# Battery_Manager.net
KiCad netlist of a schematic drawn in Altium Designer
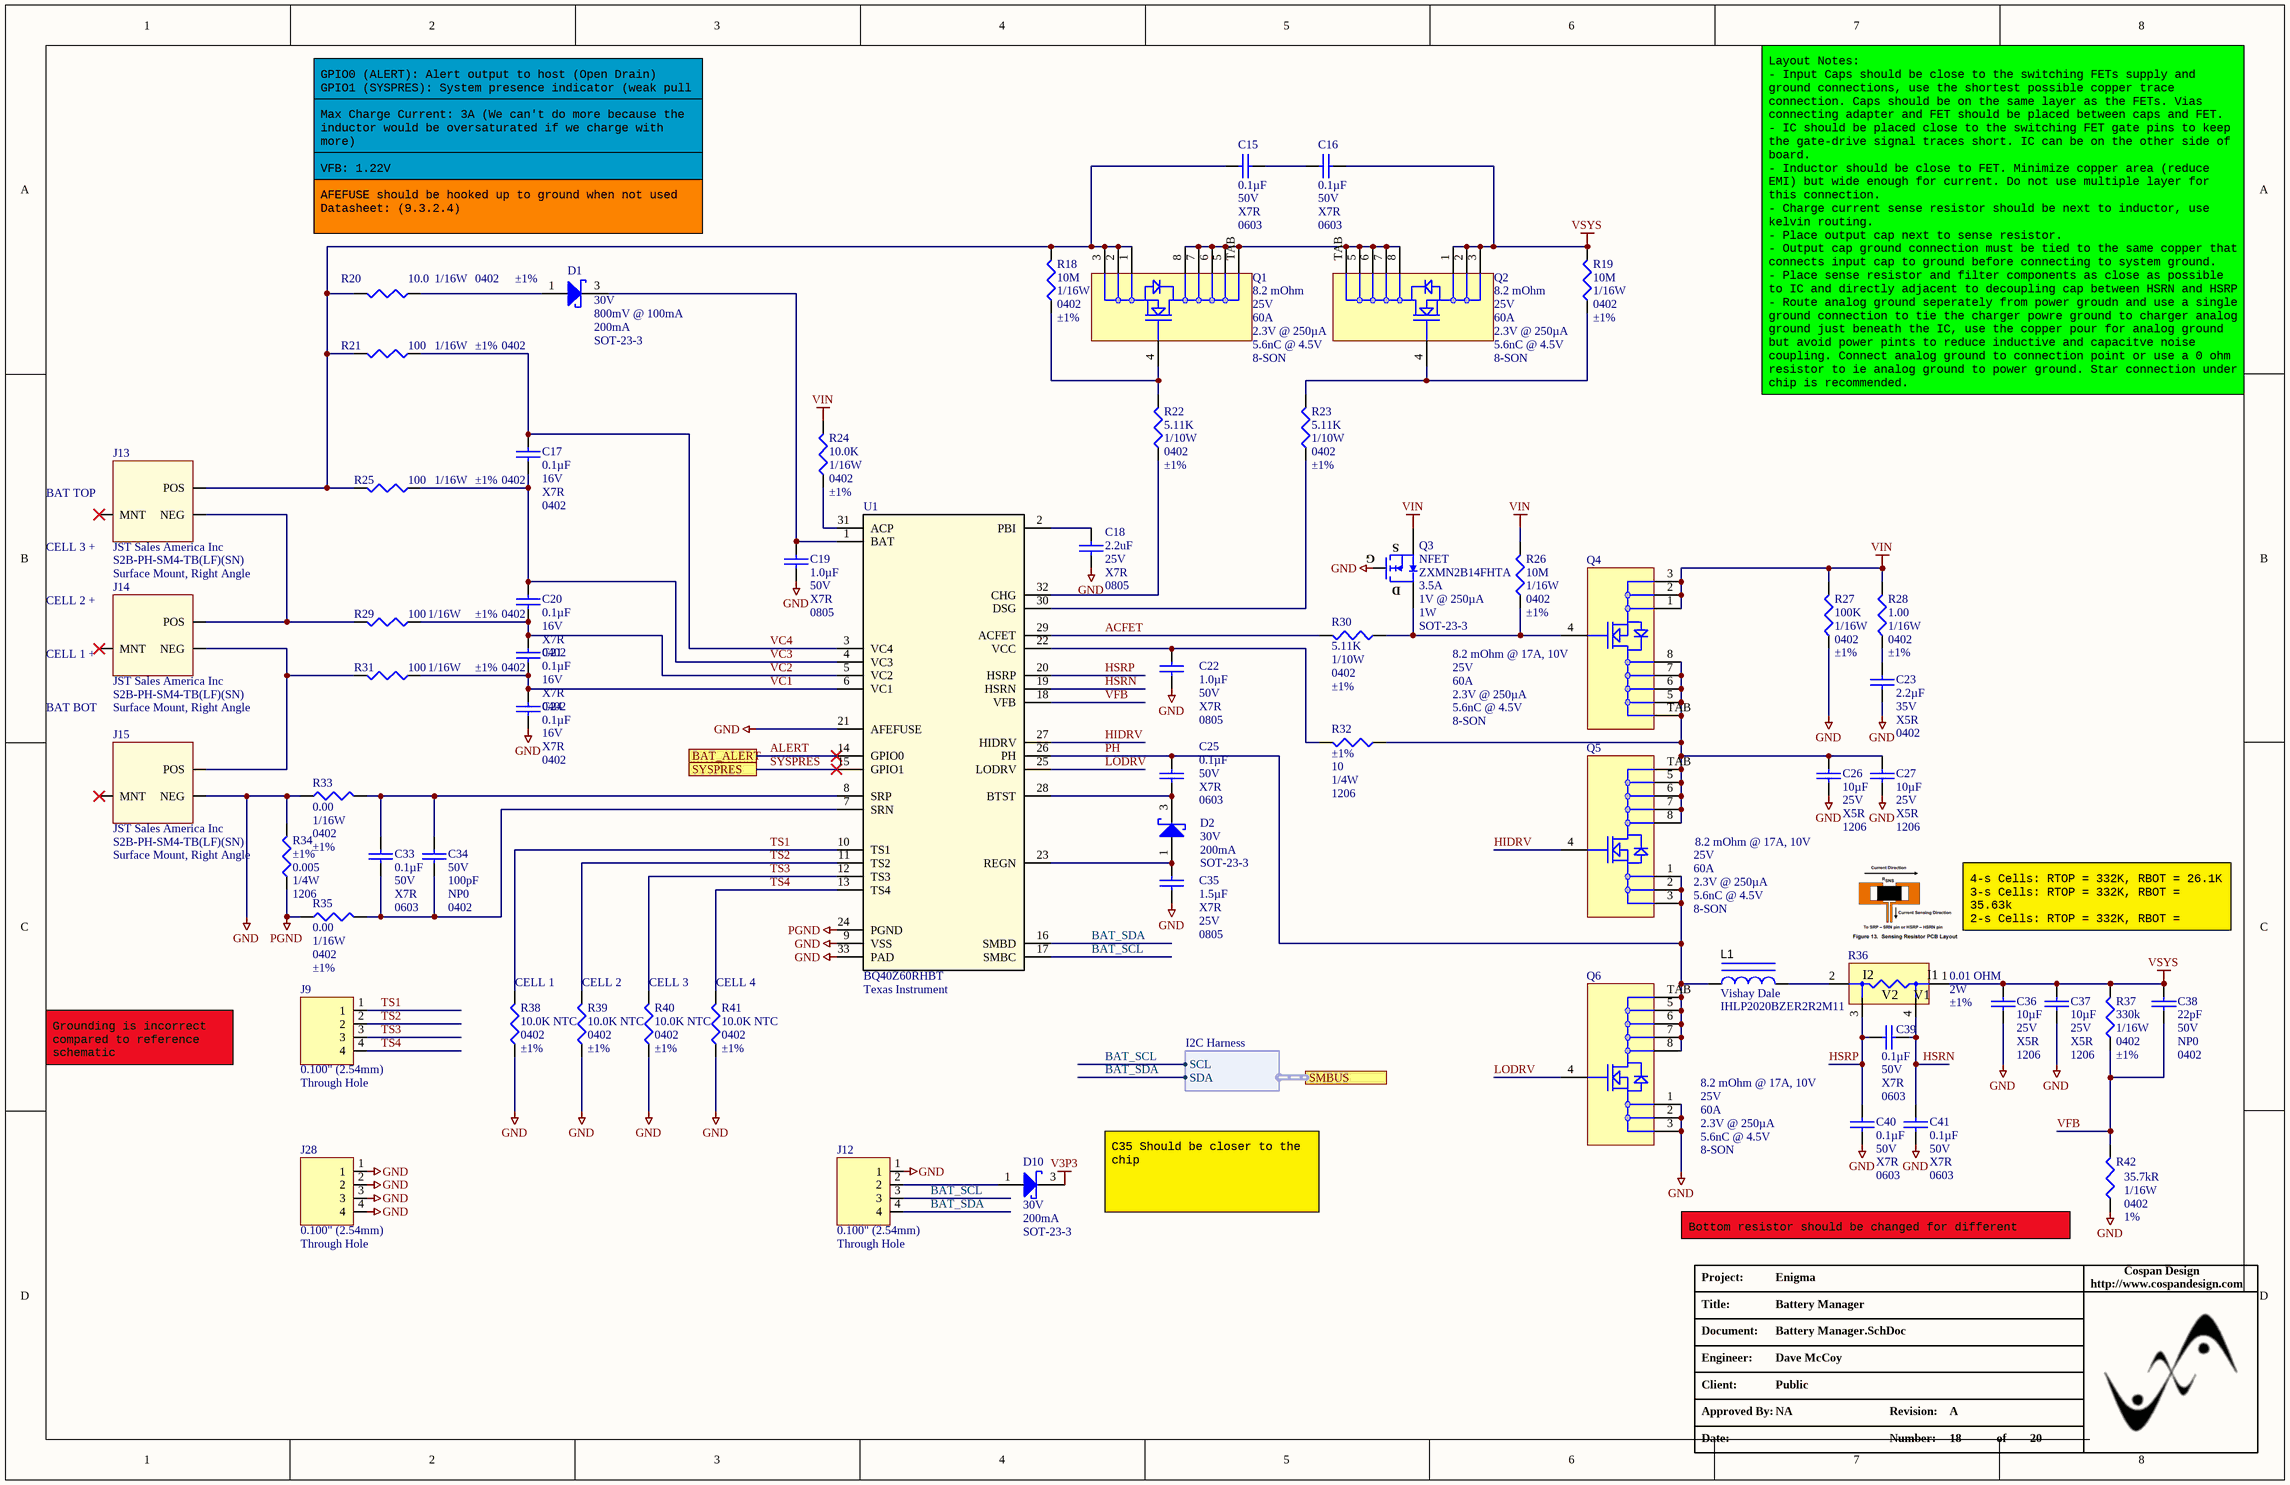
[diagram p0: Battery Manager.SchDoc]

(export (version "E")
  (design (tool "Eeschema 10.0.6"))
  (components
    (comp (ref "C15")
      (value "C_0603_0.1µF")
      (footprint "C_ERA-0603")
      (description "CAP CER 0.1UF 50V X7R 0603")
      (fields
        (field (name "MANUFACTURER") "Samsung Electro-Mechanics America, Inc.")
        (field (name "MANUFACTURER PART NUMBER") "CL10B104KB8SFNC")
        (field (name "CAPACITANCE") "0.1µF")
        (field (name "VOLTAGE - RATED") "50V")
        (field (name "TEMPERATURE COEFFICIENT") "X7R")
        (field (name "PACKAGE / CASE") "0603")
      )
      (libsource (lib "Cospan Design") (part "C_0603_0.1µF"))
    )
    (comp (ref "C16")
      (value "C_0603_0.1µF")
      (footprint "C_ERA-0603")
      (description "CAP CER 0.1UF 50V X7R 0603")
      (fields
        (field (name "MANUFACTURER") "Samsung Electro-Mechanics America, Inc.")
        (field (name "MANUFACTURER PART NUMBER") "CL10B104KB8SFNC")
        (field (name "CAPACITANCE") "0.1µF")
        (field (name "VOLTAGE - RATED") "50V")
        (field (name "TEMPERATURE COEFFICIENT") "X7R")
        (field (name "PACKAGE / CASE") "0603")
      )
      (libsource (lib "Cospan Design") (part "C_0603_0.1µF"))
    )
    (comp (ref "C17")
      (value "0.1uF")
      (footprint "C_0402")
      (description "CAP CER .10UF 16V X7R 0402")
      (fields
        (field (name "MANUFACTURER") "Murata Electronics North America")
        (field (name "MANUFACTURER PART NUMBER") "GRM155R71C104KA88J")
        (field (name "CAPACITANCE") "0.1µF")
        (field (name "VOLTAGE - RATED") "16V")
        (field (name "TEMPERATURE COEFFICIENT") "X7R")
        (field (name "PACKAGE / CASE") "0402")
      )
      (libsource (lib "Main LibraryX") (part "C_0402_0.1UF_16V"))
    )
    (comp (ref "C18")
      (value "C_0805_2.2uF_25V")
      (footprint "C_ERA-0805")
      (fields
        (field (name "MANUFACTURER") "Taiyo Yuden")
        (field (name "MANUFACTURER PART NUMBER") "TMK212B7225KG-TR")
        (field (name "TOLERANCE") "±10%")
        (field (name "CAPACITANCE") "2.2uF")
        (field (name "VOLTAGE - RATED") "25V")
        (field (name "TEMPERATURE COEFFICIENT") "X7R")
        (field (name "PACKAGE / CASE") "0805")
      )
      (libsource (lib "Cospan Design") (part "C_0805_2.2uF_25V"))
    )
    (comp (ref "C19")
      (value "1.0uF")
      (footprint "C_ERA-0805")
      (description "CAP CER 1UF 50V X7R 0805")
      (fields
        (field (name "MANUFACTURER") "Murata Electronics North America")
        (field (name "MANUFACTURER PART NUMBER") "GRM21BR71H105KA12L")
        (field (name "CAPACITANCE") "1.0µF")
        (field (name "VOLTAGE - RATED") "50V")
        (field (name "TEMPERATURE COEFFICIENT") "X7R")
        (field (name "PACKAGE / CASE") "0805")
      )
      (libsource (lib "Main Library") (part "C_0805_1.0uF_50V"))
    )
    (comp (ref "C20")
      (value "0.1uF")
      (footprint "C_0402")
      (description "CAP CER .10UF 16V X7R 0402")
      (fields
        (field (name "MANUFACTURER") "Murata Electronics North America")
        (field (name "MANUFACTURER PART NUMBER") "GRM155R71C104KA88J")
        (field (name "CAPACITANCE") "0.1µF")
        (field (name "VOLTAGE - RATED") "16V")
        (field (name "TEMPERATURE COEFFICIENT") "X7R")
        (field (name "PACKAGE / CASE") "0402")
      )
      (libsource (lib "Main LibraryX") (part "C_0402_0.1UF_16V"))
    )
    (comp (ref "C21")
      (value "0.1uF")
      (footprint "C_0402")
      (description "CAP CER .10UF 16V X7R 0402")
      (fields
        (field (name "MANUFACTURER") "Murata Electronics North America")
        (field (name "MANUFACTURER PART NUMBER") "GRM155R71C104KA88J")
        (field (name "CAPACITANCE") "0.1µF")
        (field (name "VOLTAGE - RATED") "16V")
        (field (name "TEMPERATURE COEFFICIENT") "X7R")
        (field (name "PACKAGE / CASE") "0402")
      )
      (libsource (lib "Main LibraryX") (part "C_0402_0.1UF_16V"))
    )
    (comp (ref "C22")
      (value "1.0uF")
      (footprint "C_ERA-0805")
      (description "CAP CER 1UF 50V X7R 0805")
      (fields
        (field (name "MANUFACTURER") "Murata Electronics North America")
        (field (name "MANUFACTURER PART NUMBER") "GRM21BR71H105KA12L")
        (field (name "CAPACITANCE") "1.0µF")
        (field (name "VOLTAGE - RATED") "50V")
        (field (name "TEMPERATURE COEFFICIENT") "X7R")
        (field (name "PACKAGE / CASE") "0805")
      )
      (libsource (lib "Main Library") (part "C_0805_1.0uF_50V"))
    )
    (comp (ref "C23")
      (value "C_0402_2.2uF_35V")
      (footprint "C_ERA-0402")
      (description "CAP CER 2.2UF 35V 20% X5R 0402")
      (fields
        (field (name "MANUFACTURER") "TDK Corporation")
        (field (name "MANUFACTURER PART NUMBER") "C1005X5R1V225K050BC")
        (field (name "CAPACITANCE") "2.2µF")
        (field (name "VOLTAGE - RATED") "35V")
        (field (name "TEMPERATURE COEFFICIENT") "X5R")
        (field (name "PACKAGE / CASE") "0402")
      )
      (libsource (lib "Main LibraryX") (part "C_0402_2.2uF_35V"))
    )
    (comp (ref "C24")
      (value "0.1uF")
      (footprint "C_0402")
      (description "CAP CER .10UF 16V X7R 0402")
      (fields
        (field (name "MANUFACTURER") "Murata Electronics North America")
        (field (name "MANUFACTURER PART NUMBER") "GRM155R71C104KA88J")
        (field (name "CAPACITANCE") "0.1µF")
        (field (name "VOLTAGE - RATED") "16V")
        (field (name "TEMPERATURE COEFFICIENT") "X7R")
        (field (name "PACKAGE / CASE") "0402")
      )
      (libsource (lib "Main LibraryX") (part "C_0402_0.1UF_16V"))
    )
    (comp (ref "C25")
      (value "C_0603_0.1µF")
      (footprint "C_ERA-0603")
      (description "CAP CER 0.1UF 50V X7R 0603")
      (fields
        (field (name "MANUFACTURER") "Samsung Electro-Mechanics America, Inc.")
        (field (name "MANUFACTURER PART NUMBER") "CL10B104KB8SFNC")
        (field (name "CAPACITANCE") "0.1µF")
        (field (name "VOLTAGE - RATED") "50V")
        (field (name "TEMPERATURE COEFFICIENT") "X7R")
        (field (name "PACKAGE / CASE") "0603")
      )
      (libsource (lib "Cospan Design") (part "C_0603_0.1µF"))
    )
    (comp (ref "C26")
      (value "10µF")
      (footprint "CAP-1206")
      (description "CAP CER 10UF 25V X5R 1206")
      (fields
        (field (name "MANUFACTURER") "Murata Electronics North America")
        (field (name "MANUFACTURER PART NUMBER") "GRM31CR61E106MA12L")
        (field (name "CAPACITANCE") "10µF")
        (field (name "VOLTAGE - RATED") "25V")
        (field (name "TEMPERATURE COEFFICIENT") "X5R")
        (field (name "PACKAGE / CASE") "1206")
      )
      (libsource (lib "Main Library") (part "C_1206_10UF_25V"))
    )
    (comp (ref "C27")
      (value "10µF")
      (footprint "CAP-1206")
      (description "CAP CER 10UF 25V X5R 1206")
      (fields
        (field (name "MANUFACTURER") "Murata Electronics North America")
        (field (name "MANUFACTURER PART NUMBER") "GRM31CR61E106MA12L")
        (field (name "CAPACITANCE") "10µF")
        (field (name "VOLTAGE - RATED") "25V")
        (field (name "TEMPERATURE COEFFICIENT") "X5R")
        (field (name "PACKAGE / CASE") "1206")
      )
      (libsource (lib "Main Library") (part "C_1206_10UF_25V"))
    )
    (comp (ref "C33")
      (value "C_0603_0.1µF")
      (footprint "C_ERA-0603")
      (description "CAP CER 0.1UF 50V X7R 0603")
      (fields
        (field (name "MANUFACTURER") "Samsung Electro-Mechanics America, Inc.")
        (field (name "MANUFACTURER PART NUMBER") "CL10B104KB8SFNC")
        (field (name "CAPACITANCE") "0.1µF")
        (field (name "VOLTAGE - RATED") "50V")
        (field (name "TEMPERATURE COEFFICIENT") "X7R")
        (field (name "PACKAGE / CASE") "0603")
      )
      (libsource (lib "Cospan Design") (part "C_0603_0.1µF"))
    )
    (comp (ref "C34")
      (value "100pF")
      (footprint "C_0402")
      (description "CAP CER 100PF 50V 5% C0G 0402")
      (fields
        (field (name "MANUFACTURER") "Murata Electronics North America")
        (field (name "MANUFACTURER PART NUMBER") "GRM1555C1H101JA01D")
        (field (name "VOLTAGE - RATED") "50V")
        (field (name "CAPACITANCE") "100pF")
        (field (name "TEMPERATURE COEFFICIENT") "NP0")
        (field (name "PACKAGE / CASE") "0402")
      )
      (libsource (lib "Main LibraryX") (part "C_0402_100PF"))
    )
    (comp (ref "C35")
      (value "C_0805_1.5uF_25V")
      (footprint "C_ERA-0805")
      (description "1.5µF ±10% 25V Ceramic Capacitor X7R 0805 (2012 Metric)")
      (fields
        (field (name "MANUFACTURER") "Murata Electronics North America")
        (field (name "MANUFACTURER PART NUMBER") "GRM21BR71E155KA88L")
        (field (name "CAPACITANCE") "1.5µF")
        (field (name "VOLTAGE - RATED") "X7R")
        (field (name "TEMPERATURE COEFFICIENT") "25V")
        (field (name "PACKAGE / CASE") "0805")
      )
      (libsource (lib "Cospan Design") (part "C_0805_1.5uF_25V"))
    )
    (comp (ref "C36")
      (value "10µF")
      (footprint "CAP-1206")
      (description "CAP CER 10UF 25V X5R 1206")
      (fields
        (field (name "MANUFACTURER") "Murata Electronics North America")
        (field (name "MANUFACTURER PART NUMBER") "GRM31CR61E106MA12L")
        (field (name "CAPACITANCE") "10µF")
        (field (name "VOLTAGE - RATED") "25V")
        (field (name "TEMPERATURE COEFFICIENT") "X5R")
        (field (name "PACKAGE / CASE") "1206")
      )
      (libsource (lib "Main Library") (part "C_1206_10UF_25V"))
    )
    (comp (ref "C37")
      (value "10µF")
      (footprint "CAP-1206")
      (description "CAP CER 10UF 25V X5R 1206")
      (fields
        (field (name "MANUFACTURER") "Murata Electronics North America")
        (field (name "MANUFACTURER PART NUMBER") "GRM31CR61E106MA12L")
        (field (name "CAPACITANCE") "10µF")
        (field (name "VOLTAGE - RATED") "25V")
        (field (name "TEMPERATURE COEFFICIENT") "X5R")
        (field (name "PACKAGE / CASE") "1206")
      )
      (libsource (lib "Main Library") (part "C_1206_10UF_25V"))
    )
    (comp (ref "C38")
      (value "22pF")
      (footprint "C_ERA-0402")
      (description "CAP CER 22PF 50V NP0 0402")
      (fields
        (field (name "MANUFACTURER") "Murata Electronics North America")
        (field (name "MANUFACTURER PART NUMBER") "GRM1555C1H220FA01D")
        (field (name "CAPACITANCE") "22pF")
        (field (name "VOLTAGE - RATED") "50V")
        (field (name "TEMPERATURE COEFFICIENT") "NP0")
        (field (name "PACKAGE / CASE") "0402")
      )
      (libsource (lib "Main LibraryX") (part "C_0402_22PF_50V"))
    )
    (comp (ref "C39")
      (value "C_0603_0.1µF")
      (footprint "C_ERA-0603")
      (description "CAP CER 0.1UF 50V X7R 0603")
      (fields
        (field (name "MANUFACTURER") "Samsung Electro-Mechanics America, Inc.")
        (field (name "MANUFACTURER PART NUMBER") "CL10B104KB8SFNC")
        (field (name "CAPACITANCE") "0.1µF")
        (field (name "VOLTAGE - RATED") "50V")
        (field (name "TEMPERATURE COEFFICIENT") "X7R")
        (field (name "PACKAGE / CASE") "0603")
      )
      (libsource (lib "Cospan Design") (part "C_0603_0.1µF"))
    )
    (comp (ref "C40")
      (value "C_0603_0.1µF")
      (footprint "C_ERA-0603")
      (description "CAP CER 0.1UF 50V X7R 0603")
      (fields
        (field (name "MANUFACTURER") "Samsung Electro-Mechanics America, Inc.")
        (field (name "MANUFACTURER PART NUMBER") "CL10B104KB8SFNC")
        (field (name "CAPACITANCE") "0.1µF")
        (field (name "VOLTAGE - RATED") "50V")
        (field (name "TEMPERATURE COEFFICIENT") "X7R")
        (field (name "PACKAGE / CASE") "0603")
      )
      (libsource (lib "Cospan Design") (part "C_0603_0.1µF"))
    )
    (comp (ref "C41")
      (value "C_0603_0.1µF")
      (footprint "C_ERA-0603")
      (description "CAP CER 0.1UF 50V X7R 0603")
      (fields
        (field (name "MANUFACTURER") "Samsung Electro-Mechanics America, Inc.")
        (field (name "MANUFACTURER PART NUMBER") "CL10B104KB8SFNC")
        (field (name "CAPACITANCE") "0.1µF")
        (field (name "VOLTAGE - RATED") "50V")
        (field (name "TEMPERATURE COEFFICIENT") "X7R")
        (field (name "PACKAGE / CASE") "0603")
      )
      (libsource (lib "Cospan Design") (part "C_0603_0.1µF"))
    )
    (comp (ref "D1")
      (value "BAT54")
      (footprint "SOT23")
      (description "DIODE SCHOTTKY 30V 200MA SOT-23")
      (fields
        (field (name "MANUFACTURER") "Fairchild Semiconductor")
        (field (name "VOLTAGE - DC REVERSE (VR) (MAX)") "30V")
        (field (name "VOLTAGE - FORWARD (VF) (MAX) @ IF") "800mV @ 100mA")
        (field (name "CURRENT - AVERAGE RECTIFIED (IO)") "200mA")
        (field (name "PACKAGE / CASE") "SOT-23-3")
      )
      (libsource (lib "Main Library") (part "D_SCHOTT_BAT54"))
    )
    (comp (ref "D2")
      (value "BAT54")
      (footprint "SOT23")
      (description "DIODE SCHOTTKY 30V 200MA SOT-23")
      (fields
        (field (name "MANUFACTURER") "Fairchild Semiconductor")
        (field (name "VOLTAGE - DC REVERSE (VR) (MAX)") "30V")
        (field (name "CURRENT - AVERAGE RECTIFIED (IO)") "200mA")
        (field (name "PACKAGE / CASE") "SOT-23-3")
      )
      (libsource (lib "Main Library") (part "D_SCHOTT_BAT54"))
    )
    (comp (ref "D10")
      (value "BAT54")
      (footprint "SOT23")
      (description "DIODE SCHOTTKY 30V 200MA SOT-23")
      (fields
        (field (name "MANUFACTURER") "Fairchild Semiconductor")
        (field (name "VOLTAGE - DC REVERSE (VR) (MAX)") "30V")
        (field (name "CURRENT - AVERAGE RECTIFIED (IO)") "200mA")
        (field (name "PACKAGE / CASE") "SOT-23-3")
      )
      (libsource (lib "Main Library") (part "D_SCHOTT_BAT54"))
    )
    (comp (ref "J9")
      (value "J_HDR1X4_THRHOLE_VERT")
      (footprint "HDR_1X4")
      (description "CONN HEADER .100\" 4POS TIN PCB")
      (fields
        (field (name "MANUFACTURER") "Samtec")
        (field (name "MANUFACTURER PART NUMBER") "TSW-104-07-T-S")
        (field (name "PITCH") "0.100\" (2.54mm)")
        (field (name "MOUNTING TYPE") "Through Hole")
      )
      (libsource (lib "Main Library") (part "J_HDR1X4_THRHOLE_VERT"))
    )
    (comp (ref "J12")
      (value "J_HDR1X4_THRHOLE_VERT")
      (footprint "HDR_1X4")
      (description "CONN HEADER .100\" 4POS TIN PCB")
      (fields
        (field (name "MANUFACTURER") "Samtec")
        (field (name "MANUFACTURER PART NUMBER") "TSW-104-07-T-S")
        (field (name "PITCH") "0.100\" (2.54mm)")
        (field (name "MOUNTING TYPE") "Through Hole")
      )
      (libsource (lib "Main Library") (part "J_HDR1X4_THRHOLE_VERT"))
    )
    (comp (ref "J13")
      (value "J_LIPO_BAT_CONNECTOR")
      (footprint "HDR_1X2_LIPO_BATTERY")
      (description "CONN HEADER PH SIDE 2POS 2MM SMD")
      (fields
        (field (name "MANUFACTURER") "JST Sales America Inc")
        (field (name "MANUFACTURER PART NUMBER") "S2B-PH-SM4-TB(LF)(SN)")
        (field (name "MOUNTING TYPE") "Surface Mount, Right Angle")
      )
      (libsource (lib "Main Library") (part "J_LIPO_BAT_CONNECTOR"))
    )
    (comp (ref "J14")
      (value "J_LIPO_BAT_CONNECTOR")
      (footprint "HDR_1X2_LIPO_BATTERY")
      (description "CONN HEADER PH SIDE 2POS 2MM SMD")
      (fields
        (field (name "MANUFACTURER") "JST Sales America Inc")
        (field (name "MANUFACTURER PART NUMBER") "S2B-PH-SM4-TB(LF)(SN)")
        (field (name "MOUNTING TYPE") "Surface Mount, Right Angle")
      )
      (libsource (lib "Main Library") (part "J_LIPO_BAT_CONNECTOR"))
    )
    (comp (ref "J15")
      (value "J_LIPO_BAT_CONNECTOR")
      (footprint "HDR_1X2_LIPO_BATTERY")
      (description "CONN HEADER PH SIDE 2POS 2MM SMD")
      (fields
        (field (name "MANUFACTURER") "JST Sales America Inc")
        (field (name "MANUFACTURER PART NUMBER") "S2B-PH-SM4-TB(LF)(SN)")
        (field (name "MOUNTING TYPE") "Surface Mount, Right Angle")
      )
      (libsource (lib "Main Library") (part "J_LIPO_BAT_CONNECTOR"))
    )
    (comp (ref "J28")
      (value "J_HDR1X4_THRHOLE_VERT")
      (footprint "HDR_1X4")
      (description "CONN HEADER .100\" 4POS TIN PCB")
      (fields
        (field (name "MANUFACTURER") "Samtec")
        (field (name "MANUFACTURER PART NUMBER") "TSW-104-07-T-S")
        (field (name "PITCH") "0.100\" (2.54mm)")
        (field (name "MOUNTING TYPE") "Through Hole")
      )
      (libsource (lib "Main Library") (part "J_HDR1X4_THRHOLE_VERT"))
    )
    (comp (ref "L1")
      (value "L_IHLP2020BZER2R2M11")
      (footprint "IHLP-2020BZ")
      (description "2.2µH Shielded Molded Inductor 5A 37.7 mOhm Max")
      (fields
        (field (name "TOLERANCE") "±20%")
        (field (name "MANUFACTURER") "Vishay Dale")
        (field (name "MANUFACTURER PART NUMBER") "IHLP2020BZER2R2M11")
      )
      (libsource (lib "Cospan Design") (part "L_IHLP2020BZER2R2M11"))
    )
    (comp (ref "Q1")
      (value "N-Channel Nex_FET")
      (footprint "Q_TDSON-8 NexFET")
      (description "MOSFET N-CH 25V 60A 8-SON")
      (fields
        (field (name "MANUFACTURER") "Texas Instruments")
        (field (name "MANUFACTURER PART NUMBER") "CSD16409Q3")
        (field (name "RDS ON (MAX) @ ID, VGS") "8.2 mOhm")
        (field (name "DRAIN TO SOURCE VOLTAGE (VDSS)") "25V")
        (field (name "CURRENT - CONTINUOUS DRAIN (ID) @ 25° C") "60A")
        (field (name "VGS(TH) (MAX) @ ID") "2.3V @ 250µA")
        (field (name "GATE CHARGE (QG) @ VGS") "5.6nC @ 4.5V")
        (field (name "PACKAGE / CASE") "8-SON")
      )
      (libsource (lib "Main Library") (part "Q_N-CH_8SON_60A_9.5mOHM"))
    )
    (comp (ref "Q2")
      (value "N-Channel Nex_FET")
      (footprint "Q_TDSON-8 NexFET")
      (description "MOSFET N-CH 25V 60A 8-SON")
      (fields
        (field (name "MANUFACTURER") "Texas Instruments")
        (field (name "MANUFACTURER PART NUMBER") "CSD16409Q3")
        (field (name "RDS ON (MAX) @ ID, VGS") "8.2 mOhm")
        (field (name "DRAIN TO SOURCE VOLTAGE (VDSS)") "25V")
        (field (name "CURRENT - CONTINUOUS DRAIN (ID) @ 25° C") "60A")
        (field (name "VGS(TH) (MAX) @ ID") "2.3V @ 250µA")
        (field (name "GATE CHARGE (QG) @ VGS") "5.6nC @ 4.5V")
        (field (name "PACKAGE / CASE") "8-SON")
      )
      (libsource (lib "Main Library") (part "Q_N-CH_8SON_60A_9.5mOHM"))
    )
    (comp (ref "Q3")
      (value "NFET")
      (footprint "SOT-23A")
      (description "MOSFET N-CH 20V 3.5A SOT23-3")
      (fields
        (field (name "MANUFACTURER") "Diodes/Zetex")
        (field (name "MANUFACTURER PART NUMBER") "ZXMN2B14FHTA")
        (field (name "CURRENT - CONTINUOUS DRAIN (ID) @ 25° C") "3.5A")
        (field (name "VGS(TH) (MAX) @ ID") "1V @ 250µA")
        (field (name "POWER - MAX") "1W")
        (field (name "PACKAGE / CASE") "SOT-23-3")
      )
      (libsource (lib "Main LibraryX") (part "Q_NFET_3.50A_SOT23"))
    )
    (comp (ref "Q4")
      (value "N-Channel Nex_FET")
      (footprint "Q_TDSON-8 NexFET")
      (description "MOSFET N-CH 25V 60A 8-SON")
      (fields
        (field (name "MANUFACTURER") "Texas Instruments")
        (field (name "MANUFACTURER PART NUMBER") "CSD16409Q3")
        (field (name "RDS ON (MAX) @ ID, VGS") "8.2 mOhm @ 17A, 10V")
        (field (name "DRAIN TO SOURCE VOLTAGE (VDSS)") "25V")
        (field (name "CURRENT - CONTINUOUS DRAIN (ID) @ 25° C") "60A")
        (field (name "VGS(TH) (MAX) @ ID") "2.3V @ 250µA")
        (field (name "GATE CHARGE (QG) @ VGS") "5.6nC @ 4.5V")
        (field (name "PACKAGE / CASE") "8-SON")
      )
      (libsource (lib "Main Library") (part "Q_N-CH_8SON_60A_9.5mOHM"))
    )
    (comp (ref "Q5")
      (value "N-Channel Nex_FET")
      (footprint "Q_TDSON-8 NexFET")
      (description "MOSFET N-CH 25V 60A 8-SON")
      (fields
        (field (name "MANUFACTURER") "Texas Instruments")
        (field (name "MANUFACTURER PART NUMBER") "CSD16409Q3")
        (field (name "RDS ON (MAX) @ ID, VGS") "8.2 mOhm @ 17A, 10V")
        (field (name "DRAIN TO SOURCE VOLTAGE (VDSS)") "25V")
        (field (name "CURRENT - CONTINUOUS DRAIN (ID) @ 25° C") "60A")
        (field (name "VGS(TH) (MAX) @ ID") "2.3V @ 250µA")
        (field (name "GATE CHARGE (QG) @ VGS") "5.6nC @ 4.5V")
        (field (name "PACKAGE / CASE") "8-SON")
      )
      (libsource (lib "Main Library") (part "Q_N-CH_8SON_60A_9.5mOHM"))
    )
    (comp (ref "Q6")
      (value "N-Channel Nex_FET")
      (footprint "Q_TDSON-8 NexFET")
      (description "MOSFET N-CH 25V 60A 8-SON")
      (fields
        (field (name "MANUFACTURER") "Texas Instruments")
        (field (name "MANUFACTURER PART NUMBER") "CSD16409Q3")
        (field (name "RDS ON (MAX) @ ID, VGS") "8.2 mOhm @ 17A, 10V")
        (field (name "DRAIN TO SOURCE VOLTAGE (VDSS)") "25V")
        (field (name "CURRENT - CONTINUOUS DRAIN (ID) @ 25° C") "60A")
        (field (name "VGS(TH) (MAX) @ ID") "2.3V @ 250µA")
        (field (name "GATE CHARGE (QG) @ VGS") "5.6nC @ 4.5V")
        (field (name "PACKAGE / CASE") "8-SON")
      )
      (libsource (lib "Main Library") (part "Q_N-CH_8SON_60A_9.5mOHM"))
    )
    (comp (ref "R18")
      (value "R_0402_10M")
      (footprint "R_0402")
      (description "RES SMD 10M OHM 1% 1/16W 0402")
      (fields
        (field (name "MANUFACTURER") "Yageo")
        (field (name "MANUFACTURER PART NUMBER") "RC0402FR-0710ML")
        (field (name "RESISTANCE IN OHMS") "10M")
        (field (name "POWER (WATTS)") "1/16W")
        (field (name "CASE") "0402")
        (field (name "TOLERANCE") "±1%")
      )
      (libsource (lib "Cospan Design") (part "R_0402_10M"))
    )
    (comp (ref "R19")
      (value "R_0402_10M")
      (footprint "R_0402")
      (description "RES SMD 10M OHM 1% 1/16W 0402")
      (fields
        (field (name "MANUFACTURER") "Yageo")
        (field (name "MANUFACTURER PART NUMBER") "RC0402FR-0710ML")
        (field (name "RESISTANCE IN OHMS") "10M")
        (field (name "POWER (WATTS)") "1/16W")
        (field (name "CASE") "0402")
        (field (name "TOLERANCE") "±1%")
      )
      (libsource (lib "Cospan Design") (part "R_0402_10M"))
    )
    (comp (ref "R20")
      (value "R_0402_10.0")
      (footprint "R_0402")
      (description "RES 10.0 OHM 1/16W 1% 0402 SMD")
      (fields
        (field (name "MANUFACTURER") "Yageo")
        (field (name "MANUFACTURER PART NUMBER") "RC0402FR-0710RL")
        (field (name "RESISTANCE IN OHMS") "10.0")
        (field (name "POWER (WATTS)") "1/16W")
        (field (name "CASE") "0402")
        (field (name "TOLERANCE") "±1%")
      )
      (libsource (lib "Main LibraryX") (part "R_0402_10.0"))
    )
    (comp (ref "R21")
      (value "R_0402_100.0")
      (footprint "R_0402")
      (description "RES 100 OHM 1/16W 1% 0402 SMD")
      (fields
        (field (name "MANUFACTURER") "Yageo")
        (field (name "MANUFACTURER PART NUMBER") "RC0402FR-07100RL")
        (field (name "CASE") "0402")
        (field (name "RESISTANCE IN OHMS") "100")
        (field (name "POWER (WATTS)") "1/16W")
        (field (name "TOLERANCE") "±1%")
      )
      (libsource (lib "Main LibraryX") (part "R_0402_100.0"))
    )
    (comp (ref "R22")
      (value "5.11k Ohms")
      (footprint "R_0402")
      (description "RES 5.11K OHM 1/10W 1% 0402 SMD")
      (fields
        (field (name "MANUFACTURER") "Panasonic - ECG")
        (field (name "MANUFACTURER PART NUMBER") "ERJ-2RKF5111X")
        (field (name "RESISTANCE IN OHMS") "5.11K")
        (field (name "POWER (WATTS)") "1/10W")
        (field (name "CASE") "0402")
        (field (name "TOLERANCE") "±1%")
      )
      (libsource (lib "Main Library") (part "R_0402_5.11K"))
    )
    (comp (ref "R23")
      (value "5.11k Ohms")
      (footprint "R_0402")
      (description "RES 5.11K OHM 1/10W 1% 0402 SMD")
      (fields
        (field (name "MANUFACTURER") "Panasonic - ECG")
        (field (name "MANUFACTURER PART NUMBER") "ERJ-2RKF5111X")
        (field (name "RESISTANCE IN OHMS") "5.11K")
        (field (name "POWER (WATTS)") "1/10W")
        (field (name "CASE") "0402")
        (field (name "TOLERANCE") "±1%")
      )
      (libsource (lib "Main Library") (part "R_0402_5.11K"))
    )
    (comp (ref "R24")
      (value "R_0402_10.0K")
      (footprint "R_0402")
      (description "RES 10.0K OHM 1/16W 1% 0402 SMD")
      (fields
        (field (name "MANUFACTURER") "Stackpole Electronics Inc")
        (field (name "MANUFACTURER PART NUMBER") "RMCF0402FT10K0")
        (field (name "RESISTANCE IN OHMS") "10.0K")
        (field (name "POWER (WATTS)") "1/16W")
        (field (name "CASE") "0402")
        (field (name "TOLERANCE") "±1%")
      )
      (libsource (lib "Main Library") (part "R_0402_10.0K"))
    )
    (comp (ref "R25")
      (value "R_0402_100.0")
      (footprint "R_0402")
      (description "RES 100 OHM 1/16W 1% 0402 SMD")
      (fields
        (field (name "MANUFACTURER") "Yageo")
        (field (name "MANUFACTURER PART NUMBER") "RC0402FR-07100RL")
        (field (name "CASE") "0402")
        (field (name "RESISTANCE IN OHMS") "100")
        (field (name "POWER (WATTS)") "1/16W")
        (field (name "TOLERANCE") "±1%")
      )
      (libsource (lib "Main LibraryX") (part "R_0402_100.0"))
    )
    (comp (ref "R26")
      (value "R_0402_10M")
      (footprint "R_0402")
      (description "RES SMD 10M OHM 1% 1/16W 0402")
      (fields
        (field (name "MANUFACTURER") "Yageo")
        (field (name "MANUFACTURER PART NUMBER") "RC0402FR-0710ML")
        (field (name "RESISTANCE IN OHMS") "10M")
        (field (name "POWER (WATTS)") "1/16W")
        (field (name "CASE") "0402")
        (field (name "TOLERANCE") "±1%")
      )
      (libsource (lib "Cospan Design") (part "R_0402_10M"))
    )
    (comp (ref "R27")
      (value "R_0402_100.0K")
      (footprint "R_0402")
      (description "RES 100K OHM 1/16W 1% 0402 SMD")
      (fields
        (field (name "MANUFACTURER") "Stackpole Electronics Inc")
        (field (name "MANUFACTURER PART NUMBER") "RMCF0402FT100K")
        (field (name "RESISTANCE IN OHMS") "100K")
        (field (name "POWER (WATTS)") "1/16W")
        (field (name "CASE") "0402")
        (field (name "TOLERANCE") "±1%")
      )
      (libsource (lib "Main Library") (part "R_0402_100.0K"))
    )
    (comp (ref "R28")
      (value "1.0 Ohms")
      (footprint "R_0402")
      (description "RES 1.00 OHM 1/16W 1% 0402 SMD")
      (fields
        (field (name "MANUFACTURER") "Yageo")
        (field (name "MANUFACTURER PART NUMBER") "RC0402FR-071RL")
        (field (name "RESISTANCE IN OHMS") "1.00")
        (field (name "POWER (WATTS)") "1/16W")
        (field (name "CASE") "0402")
        (field (name "TOLERANCE") "±1%")
      )
      (libsource (lib "Main Library") (part "R_0402_1.00"))
    )
    (comp (ref "R29")
      (value "R_0402_100.0")
      (footprint "R_0402")
      (description "RES 100 OHM 1/16W 1% 0402 SMD")
      (fields
        (field (name "MANUFACTURER") "Yageo")
        (field (name "MANUFACTURER PART NUMBER") "RC0402FR-07100RL")
        (field (name "CASE") "0402")
        (field (name "RESISTANCE IN OHMS") "100")
        (field (name "POWER (WATTS)") "1/16W")
        (field (name "TOLERANCE") "±1%")
      )
      (libsource (lib "Main LibraryX") (part "R_0402_100.0"))
    )
    (comp (ref "R30")
      (value "5.11k Ohms")
      (footprint "R_0402")
      (description "RES 5.11K OHM 1/10W 1% 0402 SMD")
      (fields
        (field (name "MANUFACTURER") "Panasonic - ECG")
        (field (name "MANUFACTURER PART NUMBER") "ERJ-2RKF5111X")
        (field (name "RESISTANCE IN OHMS") "5.11K")
        (field (name "POWER (WATTS)") "1/10W")
        (field (name "CASE") "0402")
        (field (name "TOLERANCE") "±1%")
      )
      (libsource (lib "Main Library") (part "R_0402_5.11K"))
    )
    (comp (ref "R31")
      (value "R_0402_100.0")
      (footprint "R_0402")
      (description "RES 100 OHM 1/16W 1% 0402 SMD")
      (fields
        (field (name "MANUFACTURER") "Yageo")
        (field (name "MANUFACTURER PART NUMBER") "RC0402FR-07100RL")
        (field (name "CASE") "0402")
        (field (name "RESISTANCE IN OHMS") "100")
        (field (name "POWER (WATTS)") "1/16W")
        (field (name "TOLERANCE") "±1%")
      )
      (libsource (lib "Main LibraryX") (part "R_0402_100.0"))
    )
    (comp (ref "R32")
      (value "R_1206_10")
      (footprint "R_1206")
      (description "RES SMD 10 OHM 1% 1/4W 1206")
      (fields
        (field (name "MANUFACTURER") "Yageo")
        (field (name "MANUFACTURER PART NUMBER") "RC1206FR-0710RL")
        (field (name "TOLERANCE") "±1%")
        (field (name "RESISTANCE IN OHMS") "10")
        (field (name "POWER (WATTS)") "1/4W")
        (field (name "CASE") "1206")
      )
      (libsource (lib "Cospan Design") (part "R_1206_10"))
    )
    (comp (ref "R33")
      (value "0.0 Ohms")
      (footprint "R_0402")
      (description "RES SMD 0.0OHM JUMPER 1/10W 0402")
      (fields
        (field (name "MANUFACTURER") "Panasonic - ECG")
        (field (name "MANUFACTURER PART NUMBER") "ERJ-2GE0R00X")
        (field (name "RESISTANCE IN OHMS") "0.00")
        (field (name "POWER (WATTS)") "1/16W")
        (field (name "CASE") "0402")
        (field (name "TOLERANCE") "±1%")
      )
      (libsource (lib "Main LibraryX") (part "R_0402_0.00"))
    )
    (comp (ref "R34")
      (value "R_1206_0.005")
      (footprint "R_1206")
      (description "RES SMD 0.005 OHM 1% 1W 1206")
      (fields
        (field (name "MANUFACTURER") "Stackpole Electronics Inc.")
        (field (name "MANUFACTURER PART NUMBER") "CSRF1206FT5L00")
        (field (name "TOLERANCE") "±1%")
        (field (name "RESISTANCE IN OHMS") "0.005")
        (field (name "POWER (WATTS)") "1/4W")
        (field (name "CASE") "1206")
      )
      (libsource (lib "Cospan Design") (part "R_1206_0.005"))
    )
    (comp (ref "R35")
      (value "0.0 Ohms")
      (footprint "R_0402")
      (description "RES SMD 0.0OHM JUMPER 1/10W 0402")
      (fields
        (field (name "MANUFACTURER") "Panasonic - ECG")
        (field (name "MANUFACTURER PART NUMBER") "ERJ-2GE0R00X")
        (field (name "RESISTANCE IN OHMS") "0.00")
        (field (name "POWER (WATTS)") "1/16W")
        (field (name "CASE") "0402")
        (field (name "TOLERANCE") "±1%")
      )
      (libsource (lib "Main LibraryX") (part "R_0402_0.00"))
    )
    (comp (ref "R36")
      (value "0.01 OHM")
      (footprint "R_LVK25_0.003")
      (description "RES SMD 0.01 OHM 1% 2W 1224")
      (fields
        (field (name "MANUFACTURER") "Ohmite")
        (field (name "MANUFACTURER PART NUMBER") "LVK25R010FER")
        (field (name "POWER (WATTS)") "2W")
        (field (name "TOLERANCE") "±1%")
      )
      (libsource (lib "Main Library") (part "R_0.010SENSE_LK20"))
    )
    (comp (ref "R37")
      (value "R_0402_330K")
      (footprint "R_0402")
      (description "RES SMD 330K OHM 1% 1/16W 0402")
      (fields
        (field (name "MANUFACTURER") "Yageo")
        (field (name "MANUFACTURER PART NUMBER") "RC0402FR-07330KL")
        (field (name "RESISTANCE IN OHMS") "330k")
        (field (name "POWER (WATTS)") "1/16W")
        (field (name "CASE") "0402")
        (field (name "TOLERANCE") "±1%")
      )
      (libsource (lib "Cospan Design") (part "R_0402_330K"))
    )
    (comp (ref "R38")
      (value "R_0402_NTC_10.0K")
      (footprint "R_0402")
      (description "NTC Thermistor 10k 0402 (1005 Metric)")
      (fields
        (field (name "MANUFACTURER") "Murata Electronics North America")
        (field (name "MANUFACTURER PART NUMBER") "NCP15XH103F03RC")
        (field (name "RESISTANCE IN OHMS") "10.0K NTC")
        (field (name "CASE") "0402")
        (field (name "TOLERANCE") "±1%")
      )
      (libsource (lib "Cospan Design") (part "R_0402_NTC_10.0K"))
    )
    (comp (ref "R39")
      (value "R_0402_NTC_10.0K")
      (footprint "R_0402")
      (description "NTC Thermistor 10k 0402 (1005 Metric)")
      (fields
        (field (name "MANUFACTURER") "Murata Electronics North America")
        (field (name "MANUFACTURER PART NUMBER") "NCP15XH103F03RC")
        (field (name "RESISTANCE IN OHMS") "10.0K NTC")
        (field (name "CASE") "0402")
        (field (name "TOLERANCE") "±1%")
      )
      (libsource (lib "Cospan Design") (part "R_0402_NTC_10.0K"))
    )
    (comp (ref "R40")
      (value "R_0402_NTC_10.0K")
      (footprint "R_0402")
      (description "NTC Thermistor 10k 0402 (1005 Metric)")
      (fields
        (field (name "MANUFACTURER") "Murata Electronics North America")
        (field (name "MANUFACTURER PART NUMBER") "NCP15XH103F03RC")
        (field (name "RESISTANCE IN OHMS") "10.0K NTC")
        (field (name "CASE") "0402")
        (field (name "TOLERANCE") "±1%")
      )
      (libsource (lib "Cospan Design") (part "R_0402_NTC_10.0K"))
    )
    (comp (ref "R41")
      (value "R_0402_NTC_10.0K")
      (footprint "R_0402")
      (description "NTC Thermistor 10k 0402 (1005 Metric)")
      (fields
        (field (name "MANUFACTURER") "Murata Electronics North America")
        (field (name "MANUFACTURER PART NUMBER") "NCP15XH103F03RC")
        (field (name "RESISTANCE IN OHMS") "10.0K NTC")
        (field (name "CASE") "0402")
        (field (name "TOLERANCE") "±1%")
      )
      (libsource (lib "Cospan Design") (part "R_0402_NTC_10.0K"))
    )
    (comp (ref "R42")
      (value "R_0402_35.7K")
      (footprint "R_0402")
      (description "RES SMD 35.7K OHM 1% 1/16W 0402")
      (fields
        (field (name "POWER RATING") "1/16W")
        (field (name "TOLERANCE") "1%")
        (field (name "CASE/PACKAGE") "0402")
        (field (name "RESISTANCE") "35.7kR")
      )
      (libsource (lib "Cospan Design") (part "R_0402_35.7K"))
    )
    (comp (ref "U1")
      (value "U_BQ40Z60RHBR")
      (footprint "RHB0032E")
      (description "IC BATTERY MANAGER 32VQFN")
      (fields
        (field (name "MANUFACTURER PART NUMBER") "BQ40Z60RHBT")
        (field (name "MANUFACTURER") "Texas Instrument")
      )
      (libsource (lib "Cospan Design") (part "U_BQ40Z60RHBR"))
    )
  )
  (nets
    (net (code "3") (name "/ACFET") (class "Default")
      (node (ref "R30") (pin "1") (pinfunction "1_1") (pintype "passive"))
      (node (ref "U1") (pin "29") (pinfunction "ACFET_29") (pintype "passive"))
    )
    (net (code "4") (name "/ALERT") (class "Default")
      (node (ref "U1") (pin "14") (pinfunction "GPIO0_14") (pintype "passive+no_connect"))
    )
    (net (code "5") (name "/BAT_SCL") (class "Default")
      (node (ref "J12") (pin "3") (pinfunction "3_3") (pintype "passive"))
      (node (ref "U1") (pin "17") (pinfunction "SMBC_17") (pintype "passive"))
    )
    (net (code "6") (name "/BAT_SDA") (class "Default")
      (node (ref "J12") (pin "4") (pinfunction "4_4") (pintype "passive"))
      (node (ref "U1") (pin "16") (pinfunction "SMBD_16") (pintype "passive"))
    )
    (net (code "7") (name "/HIDRV") (class "Default")
      (node (ref "Q5") (pin "4") (pinfunction "G1_4") (pintype "passive"))
      (node (ref "U1") (pin "27") (pinfunction "HIDRV_27") (pintype "passive"))
    )
    (net (code "8") (name "/HSRN") (class "Default")
      (node (ref "C39") (pin "2") (pinfunction "2_2") (pintype "passive"))
      (node (ref "C41") (pin "1") (pinfunction "1_1") (pintype "passive"))
      (node (ref "R36") (pin "4") (pinfunction "V1_4") (pintype "passive"))
      (node (ref "U1") (pin "19") (pinfunction "HSRN_19") (pintype "passive"))
    )
    (net (code "9") (name "/HSRP") (class "Default")
      (node (ref "C39") (pin "1") (pinfunction "1_1") (pintype "passive"))
      (node (ref "C40") (pin "1") (pinfunction "1_1") (pintype "passive"))
      (node (ref "R36") (pin "3") (pinfunction "V2_3") (pintype "passive"))
      (node (ref "U1") (pin "20") (pinfunction "HSRP_20") (pintype "passive"))
    )
    (net (code "10") (name "/LODRV") (class "Default")
      (node (ref "Q6") (pin "4") (pinfunction "G1_4") (pintype "passive"))
      (node (ref "U1") (pin "25") (pinfunction "LODRV_25") (pintype "passive"))
    )
    (net (code "11") (name "/PH") (class "Default")
      (node (ref "C25") (pin "1") (pinfunction "1_1") (pintype "passive"))
      (node (ref "L1") (pin "2") (pinfunction "2_2") (pintype "passive"))
      (node (ref "Q5") (pin "1") (pinfunction "S1_1") (pintype "passive"))
      (node (ref "Q5") (pin "2") (pintype "passive"))
      (node (ref "Q5") (pin "3") (pintype "passive"))
      (node (ref "Q6") (pin "5") (pintype "passive"))
      (node (ref "Q6") (pin "6") (pintype "passive"))
      (node (ref "Q6") (pin "7") (pinfunction "D2a_7") (pintype "passive"))
      (node (ref "Q6") (pin "8") (pinfunction "D2b_8") (pintype "passive"))
      (node (ref "Q6") (pin "TAB") (pintype "passive"))
      (node (ref "U1") (pin "26") (pinfunction "PH_26") (pintype "passive"))
    )
    (net (code "12") (name "/SYSPRES") (class "Default")
      (node (ref "U1") (pin "15") (pinfunction "GPIO1_15") (pintype "passive+no_connect"))
    )
    (net (code "13") (name "/TS1") (class "Default")
      (node (ref "J9") (pin "1") (pinfunction "1_1") (pintype "passive"))
      (node (ref "R38") (pin "1") (pinfunction "1_1") (pintype "passive"))
      (node (ref "U1") (pin "10") (pinfunction "TS1_10") (pintype "passive"))
    )
    (net (code "14") (name "/TS2") (class "Default")
      (node (ref "J9") (pin "2") (pinfunction "2_2") (pintype "passive"))
      (node (ref "R39") (pin "1") (pinfunction "1_1") (pintype "passive"))
      (node (ref "U1") (pin "11") (pinfunction "TS2_11") (pintype "passive"))
    )
    (net (code "15") (name "/TS3") (class "Default")
      (node (ref "J9") (pin "3") (pinfunction "3_3") (pintype "passive"))
      (node (ref "R40") (pin "1") (pinfunction "1_1") (pintype "passive"))
      (node (ref "U1") (pin "12") (pinfunction "TS3_12") (pintype "passive"))
    )
    (net (code "16") (name "/TS4") (class "Default")
      (node (ref "J9") (pin "4") (pinfunction "4_4") (pintype "passive"))
      (node (ref "R41") (pin "1") (pinfunction "1_1") (pintype "passive"))
      (node (ref "U1") (pin "13") (pinfunction "TS4_13") (pintype "passive"))
    )
    (net (code "17") (name "/VC1") (class "Default")
      (node (ref "C21") (pin "2") (pinfunction "2_2") (pintype "passive"))
      (node (ref "C24") (pin "1") (pinfunction "1_1") (pintype "passive"))
      (node (ref "R31") (pin "2") (pinfunction "2_2") (pintype "passive"))
      (node (ref "U1") (pin "6") (pinfunction "VC1_6") (pintype "passive"))
    )
    (net (code "18") (name "/VC2") (class "Default")
      (node (ref "C20") (pin "2") (pinfunction "2_2") (pintype "passive"))
      (node (ref "C21") (pin "1") (pinfunction "1_1") (pintype "passive"))
      (node (ref "R29") (pin "2") (pinfunction "2_2") (pintype "passive"))
      (node (ref "U1") (pin "5") (pinfunction "VC2_5") (pintype "passive"))
    )
    (net (code "19") (name "/VC3") (class "Default")
      (node (ref "C17") (pin "2") (pinfunction "2_2") (pintype "passive"))
      (node (ref "C20") (pin "1") (pinfunction "1_1") (pintype "passive"))
      (node (ref "R25") (pin "2") (pinfunction "2_2") (pintype "passive"))
      (node (ref "U1") (pin "4") (pinfunction "VC3_4") (pintype "passive"))
    )
    (net (code "20") (name "/VC4") (class "Default")
      (node (ref "C17") (pin "1") (pinfunction "1_1") (pintype "passive"))
      (node (ref "R21") (pin "2") (pinfunction "2_2") (pintype "passive"))
      (node (ref "U1") (pin "3") (pinfunction "VC4_3") (pintype "passive"))
    )
    (net (code "21") (name "/VFB") (class "Default")
      (node (ref "C38") (pin "1") (pinfunction "1_1") (pintype "passive"))
      (node (ref "R37") (pin "2") (pinfunction "2_2") (pintype "passive"))
      (node (ref "R42") (pin "1") (pinfunction "1_1") (pintype "passive"))
      (node (ref "U1") (pin "18") (pinfunction "VFB_18") (pintype "passive"))
    )
    (net (code "23") (name "GND") (class "Default")
      (node (ref "C18") (pin "1") (pinfunction "1_1") (pintype "passive"))
      (node (ref "C19") (pin "1") (pinfunction "1_1") (pintype "passive"))
      (node (ref "C22") (pin "1") (pinfunction "1_1") (pintype "passive"))
      (node (ref "C23") (pin "1") (pinfunction "1_1") (pintype "passive"))
      (node (ref "C24") (pin "2") (pinfunction "2_2") (pintype "passive"))
      (node (ref "C26") (pin "1") (pinfunction "1_1") (pintype "passive"))
      (node (ref "C27") (pin "1") (pinfunction "1_1") (pintype "passive"))
      (node (ref "C35") (pin "1") (pinfunction "1_1") (pintype "passive"))
      (node (ref "C36") (pin "2") (pinfunction "2_2") (pintype "passive"))
      (node (ref "C37") (pin "2") (pinfunction "2_2") (pintype "passive"))
      (node (ref "C40") (pin "2") (pinfunction "2_2") (pintype "passive"))
      (node (ref "C41") (pin "2") (pinfunction "2_2") (pintype "passive"))
      (node (ref "J12") (pin "1") (pinfunction "1_1") (pintype "passive"))
      (node (ref "J15") (pin "2") (pinfunction "NEG_2") (pintype "passive"))
      (node (ref "J28") (pin "1") (pinfunction "1_1") (pintype "passive"))
      (node (ref "J28") (pin "2") (pinfunction "2_2") (pintype "passive"))
      (node (ref "J28") (pin "3") (pinfunction "3_3") (pintype "passive"))
      (node (ref "J28") (pin "4") (pinfunction "4_4") (pintype "passive"))
      (node (ref "Q3") (pin "1") (pinfunction "G_1") (pintype "passive"))
      (node (ref "Q6") (pin "1") (pinfunction "S1_1") (pintype "passive"))
      (node (ref "Q6") (pin "2") (pintype "passive"))
      (node (ref "Q6") (pin "3") (pintype "passive"))
      (node (ref "R27") (pin "2") (pinfunction "2_2") (pintype "passive"))
      (node (ref "R33") (pin "2") (pinfunction "2_2") (pintype "passive"))
      (node (ref "R34") (pin "1") (pinfunction "1_1") (pintype "passive"))
      (node (ref "R38") (pin "2") (pinfunction "2_2") (pintype "passive"))
      (node (ref "R39") (pin "2") (pinfunction "2_2") (pintype "passive"))
      (node (ref "R40") (pin "2") (pinfunction "2_2") (pintype "passive"))
      (node (ref "R41") (pin "2") (pinfunction "2_2") (pintype "passive"))
      (node (ref "R42") (pin "2") (pinfunction "2_2") (pintype "passive"))
      (node (ref "U1") (pin "21") (pinfunction "AFEFUSE_21") (pintype "passive"))
      (node (ref "U1") (pin "33") (pinfunction "PAD_33") (pintype "passive"))
      (node (ref "U1") (pin "9") (pinfunction "VSS_9") (pintype "passive"))
    )
    (net (code "24") (name "Net-(C15-Pad1)") (class "Default")
      (node (ref "C15") (pin "1") (pinfunction "1_1") (pintype "passive"))
      (node (ref "C16") (pin "2") (pinfunction "2_2") (pintype "passive"))
    )
    (net (code "25") (name "Net-(C23-Pad2)") (class "Default")
      (node (ref "C23") (pin "2") (pinfunction "2_2") (pintype "passive"))
      (node (ref "R28") (pin "2") (pinfunction "2_2") (pintype "passive"))
    )
    (net (code "26") (name "Net-(D1-A)") (class "Default")
      (node (ref "D1") (pin "1") (pinfunction "A_1") (pintype "passive"))
      (node (ref "R20") (pin "2") (pinfunction "2_2") (pintype "passive"))
    )
    (net (code "27") (name "Net-(D1-K)") (class "Default")
      (node (ref "C19") (pin "2") (pinfunction "2_2") (pintype "passive"))
      (node (ref "D1") (pin "3") (pinfunction "K_3") (pintype "passive"))
      (node (ref "U1") (pin "1") (pinfunction "BAT_1") (pintype "passive"))
    )
    (net (code "28") (name "Net-(D2-A)") (class "Default")
      (node (ref "C35") (pin "2") (pinfunction "2_2") (pintype "passive"))
      (node (ref "D2") (pin "1") (pinfunction "A_1") (pintype "passive"))
      (node (ref "U1") (pin "23") (pinfunction "REGN_23") (pintype "passive"))
    )
    (net (code "29") (name "Net-(D2-K)") (class "Default")
      (node (ref "C25") (pin "2") (pinfunction "2_2") (pintype "passive"))
      (node (ref "D2") (pin "3") (pinfunction "K_3") (pintype "passive"))
      (node (ref "U1") (pin "28") (pinfunction "BTST_28") (pintype "passive"))
    )
    (net (code "30") (name "Net-(D10-A)") (class "Default")
      (node (ref "D10") (pin "1") (pinfunction "A_1") (pintype "passive"))
      (node (ref "J12") (pin "2") (pinfunction "2_2") (pintype "passive"))
    )
    (net (code "31") (name "Net-(J13-NEG)") (class "Default")
      (node (ref "J13") (pin "2") (pinfunction "NEG_2") (pintype "passive"))
      (node (ref "J14") (pin "1") (pinfunction "POS_1") (pintype "passive"))
      (node (ref "R29") (pin "1") (pinfunction "1_1") (pintype "passive"))
    )
    (net (code "32") (name "Net-(J13-POS)") (class "Default")
      (node (ref "C15") (pin "2") (pinfunction "2_2") (pintype "passive"))
      (node (ref "J13") (pin "1") (pinfunction "POS_1") (pintype "passive"))
      (node (ref "Q1") (pin "1") (pinfunction "S1_1") (pintype "passive"))
      (node (ref "Q1") (pin "2") (pintype "passive"))
      (node (ref "Q1") (pin "3") (pintype "passive"))
      (node (ref "R18") (pin "1") (pinfunction "1_1") (pintype "passive"))
      (node (ref "R20") (pin "1") (pinfunction "1_1") (pintype "passive"))
      (node (ref "R21") (pin "1") (pinfunction "1_1") (pintype "passive"))
      (node (ref "R25") (pin "1") (pinfunction "1_1") (pintype "passive"))
    )
    (net (code "33") (name "Net-(J14-NEG)") (class "Default")
      (node (ref "J14") (pin "2") (pinfunction "NEG_2") (pintype "passive"))
      (node (ref "J15") (pin "1") (pinfunction "POS_1") (pintype "passive"))
      (node (ref "R31") (pin "1") (pinfunction "1_1") (pintype "passive"))
    )
    (net (code "34") (name "Net-(Q1-D2a)") (class "Default")
      (node (ref "Q1") (pin "5") (pintype "passive"))
      (node (ref "Q1") (pin "6") (pintype "passive"))
      (node (ref "Q1") (pin "7") (pinfunction "D2a_7") (pintype "passive"))
      (node (ref "Q1") (pin "8") (pinfunction "D2b_8") (pintype "passive"))
      (node (ref "Q1") (pin "TAB") (pintype "passive"))
      (node (ref "Q2") (pin "5") (pintype "passive"))
      (node (ref "Q2") (pin "6") (pintype "passive"))
      (node (ref "Q2") (pin "7") (pinfunction "D2a_7") (pintype "passive"))
      (node (ref "Q2") (pin "8") (pinfunction "D2b_8") (pintype "passive"))
      (node (ref "Q2") (pin "TAB") (pintype "passive"))
    )
    (net (code "35") (name "Net-(Q1-G1)") (class "Default")
      (node (ref "Q1") (pin "4") (pinfunction "G1_4") (pintype "passive"))
      (node (ref "R18") (pin "2") (pinfunction "2_2") (pintype "passive"))
      (node (ref "R22") (pin "1") (pinfunction "1_1") (pintype "passive"))
    )
    (net (code "36") (name "Net-(Q2-G1)") (class "Default")
      (node (ref "Q2") (pin "4") (pinfunction "G1_4") (pintype "passive"))
      (node (ref "R19") (pin "2") (pinfunction "2_2") (pintype "passive"))
      (node (ref "R23") (pin "1") (pinfunction "1_1") (pintype "passive"))
    )
    (net (code "37") (name "Net-(Q3-D)") (class "Default")
      (node (ref "Q3") (pin "3") (pinfunction "D_3") (pintype "passive"))
      (node (ref "Q4") (pin "4") (pinfunction "G1_4") (pintype "passive"))
      (node (ref "R26") (pin "2") (pinfunction "2_2") (pintype "passive"))
      (node (ref "R30") (pin "2") (pinfunction "2_2") (pintype "passive"))
    )
    (net (code "38") (name "Net-(Q4-D2a)") (class "Default")
      (node (ref "C26") (pin "2") (pinfunction "2_2") (pintype "passive"))
      (node (ref "C27") (pin "2") (pinfunction "2_2") (pintype "passive"))
      (node (ref "Q4") (pin "5") (pintype "passive"))
      (node (ref "Q4") (pin "6") (pintype "passive"))
      (node (ref "Q4") (pin "7") (pinfunction "D2a_7") (pintype "passive"))
      (node (ref "Q4") (pin "8") (pinfunction "D2b_8") (pintype "passive"))
      (node (ref "Q4") (pin "TAB") (pintype "passive"))
      (node (ref "Q5") (pin "5") (pintype "passive"))
      (node (ref "Q5") (pin "6") (pintype "passive"))
      (node (ref "Q5") (pin "7") (pinfunction "D2a_7") (pintype "passive"))
      (node (ref "Q5") (pin "8") (pinfunction "D2b_8") (pintype "passive"))
      (node (ref "Q5") (pin "TAB") (pintype "passive"))
      (node (ref "R32") (pin "2") (pinfunction "2_2") (pintype "passive"))
    )
    (net (code "39") (name "Net-(R36-I2)") (class "Default")
      (node (ref "L1") (pin "1") (pinfunction "1_1") (pintype "passive"))
      (node (ref "R36") (pin "2") (pinfunction "I2_2") (pintype "passive"))
    )
    (net (code "40") (name "Net-(U1-ACP)") (class "Default")
      (node (ref "R24") (pin "2") (pinfunction "2_2") (pintype "passive"))
      (node (ref "U1") (pin "31") (pinfunction "ACP_31") (pintype "passive"))
    )
    (net (code "41") (name "Net-(U1-CHG)") (class "Default")
      (node (ref "R22") (pin "2") (pinfunction "2_2") (pintype "passive"))
      (node (ref "U1") (pin "32") (pinfunction "CHG_32") (pintype "passive"))
    )
    (net (code "42") (name "Net-(U1-DSG)") (class "Default")
      (node (ref "R23") (pin "2") (pinfunction "2_2") (pintype "passive"))
      (node (ref "U1") (pin "30") (pinfunction "DSG_30") (pintype "passive"))
    )
    (net (code "43") (name "Net-(U1-PBI)") (class "Default")
      (node (ref "C18") (pin "2") (pinfunction "2_2") (pintype "passive"))
      (node (ref "U1") (pin "2") (pinfunction "PBI_2") (pintype "passive"))
    )
    (net (code "44") (name "Net-(U1-SRN)") (class "Default")
      (node (ref "C33") (pin "1") (pinfunction "1_1") (pintype "passive"))
      (node (ref "C34") (pin "1") (pinfunction "1_1") (pintype "passive"))
      (node (ref "R35") (pin "1") (pinfunction "1_1") (pintype "passive"))
      (node (ref "U1") (pin "7") (pinfunction "SRN_7") (pintype "passive"))
    )
    (net (code "45") (name "Net-(U1-SRP)") (class "Default")
      (node (ref "C33") (pin "2") (pinfunction "2_2") (pintype "passive"))
      (node (ref "C34") (pin "2") (pinfunction "2_2") (pintype "passive"))
      (node (ref "R33") (pin "1") (pinfunction "1_1") (pintype "passive"))
      (node (ref "U1") (pin "8") (pinfunction "SRP_8") (pintype "passive"))
    )
    (net (code "46") (name "Net-(U1-VCC)") (class "Default")
      (node (ref "C22") (pin "2") (pinfunction "2_2") (pintype "passive"))
      (node (ref "R32") (pin "1") (pinfunction "1_1") (pintype "passive"))
      (node (ref "U1") (pin "22") (pinfunction "VCC_22") (pintype "passive"))
    )
    (net (code "47") (name "PGND") (class "Default")
      (node (ref "R34") (pin "2") (pinfunction "2_2") (pintype "passive"))
      (node (ref "R35") (pin "2") (pinfunction "2_2") (pintype "passive"))
      (node (ref "U1") (pin "24") (pinfunction "PGND_24") (pintype "passive"))
    )
    (net (code "48") (name "V3P3") (class "Default")
      (node (ref "D10") (pin "3") (pinfunction "K_3") (pintype "passive"))
    )
    (net (code "49") (name "VIN") (class "Default")
      (node (ref "Q3") (pin "2") (pinfunction "S_2") (pintype "passive"))
      (node (ref "Q4") (pin "1") (pinfunction "S1_1") (pintype "passive"))
      (node (ref "Q4") (pin "2") (pintype "passive"))
      (node (ref "Q4") (pin "3") (pintype "passive"))
      (node (ref "R24") (pin "1") (pinfunction "1_1") (pintype "passive"))
      (node (ref "R26") (pin "1") (pinfunction "1_1") (pintype "passive"))
      (node (ref "R27") (pin "1") (pinfunction "1_1") (pintype "passive"))
      (node (ref "R28") (pin "1") (pinfunction "1_1") (pintype "passive"))
    )
    (net (code "50") (name "VSYS") (class "Default")
      (node (ref "C16") (pin "1") (pinfunction "1_1") (pintype "passive"))
      (node (ref "C36") (pin "1") (pinfunction "1_1") (pintype "passive"))
      (node (ref "C37") (pin "1") (pinfunction "1_1") (pintype "passive"))
      (node (ref "C38") (pin "2") (pinfunction "2_2") (pintype "passive"))
      (node (ref "Q2") (pin "1") (pinfunction "S1_1") (pintype "passive"))
      (node (ref "Q2") (pin "2") (pintype "passive"))
      (node (ref "Q2") (pin "3") (pintype "passive"))
      (node (ref "R19") (pin "1") (pinfunction "1_1") (pintype "passive"))
      (node (ref "R36") (pin "1") (pinfunction "I1_1") (pintype "passive"))
      (node (ref "R37") (pin "1") (pinfunction "1_1") (pintype "passive"))
    )
    (net (code "51") (name "unconnected-(J13-PadMNT)") (class "Default")
      (node (ref "J13") (pin "MNT") (pinfunction "MNT_MNT") (pintype "passive+no_connect"))
    )
    (net (code "52") (name "unconnected-(J14-PadMNT)") (class "Default")
      (node (ref "J14") (pin "MNT") (pinfunction "MNT_MNT") (pintype "passive+no_connect"))
    )
    (net (code "53") (name "unconnected-(J15-PadMNT)") (class "Default")
      (node (ref "J15") (pin "MNT") (pinfunction "MNT_MNT") (pintype "passive+no_connect"))
    )
  )
)
